# Controller_Board_Interface.net
KiCad netlist of a schematic drawn in Altium Designer
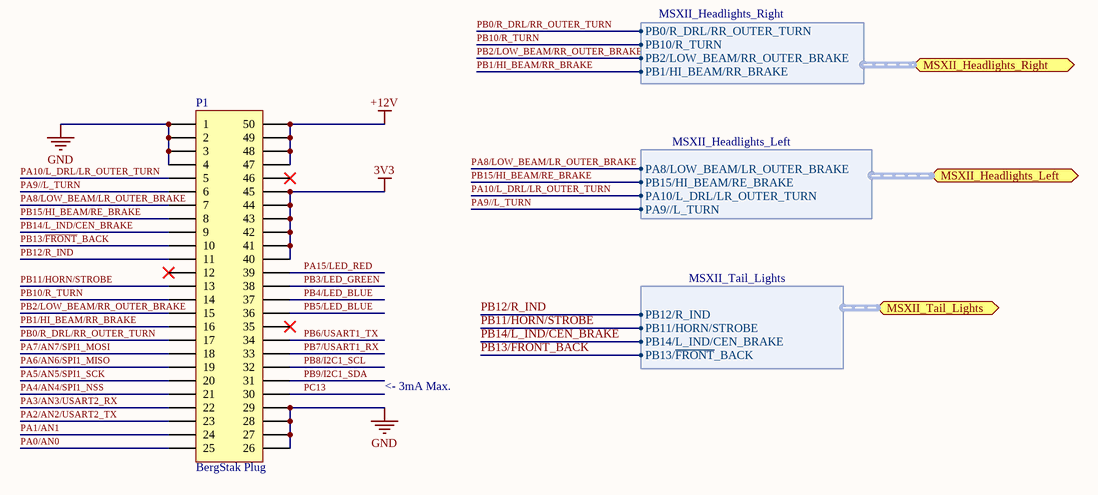
[diagram p0: Controller_Board_Interface.SchDoc]

(export (version "E")
  (design (tool "Eeschema 10.0.6"))
  (components
    (comp (ref "P1")
      (value "CONN 50POS Bergstak Plug 0.02\"")
      (footprint "CONN, Bergstak 50 Pos Plug")
      (description "50 Position Connector Plug, Outer Shroud Contacts Surface Mount Gold")
      (fields (field (name "SERIES") "BergStak Plug"))
      (libsource (lib "Schematic Diagrams") (part "CONN 50POS Bergstak Plug 0.02{dblquote}"))
    )
  )
  (nets
    (net (code "4") (name "+12V") (class "Default")
      (node (ref "P1") (pin "47") (pinfunction "47_47") (pintype "passive"))
      (node (ref "P1") (pin "48") (pinfunction "48_48") (pintype "passive"))
      (node (ref "P1") (pin "49") (pinfunction "49_49") (pintype "passive"))
      (node (ref "P1") (pin "50") (pinfunction "50_50") (pintype "passive"))
    )
    (net (code "5") (name "/PA0{slash}AN0") (class "Default")
      (node (ref "P1") (pin "25") (pinfunction "25_25") (pintype "passive"))
    )
    (net (code "6") (name "/PA1{slash}AN1") (class "Default")
      (node (ref "P1") (pin "24") (pinfunction "24_24") (pintype "passive"))
    )
    (net (code "7") (name "/PA2{slash}AN2{slash}USART2_TX") (class "Default")
      (node (ref "P1") (pin "23") (pinfunction "23_23") (pintype "passive"))
    )
    (net (code "8") (name "/PA3{slash}AN3{slash}USART2_RX") (class "Default")
      (node (ref "P1") (pin "22") (pinfunction "22_22") (pintype "passive"))
    )
    (net (code "9") (name "/PA4{slash}AN4{slash}SPI1_NSS") (class "Default")
      (node (ref "P1") (pin "21") (pinfunction "21_21") (pintype "passive"))
    )
    (net (code "10") (name "/PA5{slash}AN5{slash}SPI1_SCK") (class "Default")
      (node (ref "P1") (pin "20") (pinfunction "20_20") (pintype "passive"))
    )
    (net (code "11") (name "/PA6{slash}AN6{slash}SPI1_MISO") (class "Default")
      (node (ref "P1") (pin "19") (pinfunction "19_19") (pintype "passive"))
    )
    (net (code "12") (name "/PA7{slash}AN7{slash}SPI1_MOSI") (class "Default")
      (node (ref "P1") (pin "18") (pinfunction "18_18") (pintype "passive"))
    )
    (net (code "13") (name "/PA8{slash}LOW_BEAM{slash}LR_OUTER_BRAKE") (class "Default")
      (node (ref "P1") (pin "7") (pinfunction "7_7") (pintype "passive"))
    )
    (net (code "14") (name "/PA9{slash}{slash}L_TURN") (class "Default")
      (node (ref "P1") (pin "6") (pinfunction "6_6") (pintype "passive"))
    )
    (net (code "15") (name "/PA10{slash}L_DRL{slash}LR_OUTER_TURN") (class "Default")
      (node (ref "P1") (pin "5") (pinfunction "5_5") (pintype "passive"))
    )
    (net (code "16") (name "/PA15{slash}LED_RED") (class "Default")
      (node (ref "P1") (pin "39") (pinfunction "39_39") (pintype "passive"))
    )
    (net (code "17") (name "/PB0{slash}R_DRL{slash}RR_OUTER_TURN") (class "Default")
      (node (ref "P1") (pin "17") (pinfunction "17_17") (pintype "passive"))
    )
    (net (code "18") (name "/PB1{slash}HI_BEAM{slash}RR_BRAKE") (class "Default")
      (node (ref "P1") (pin "16") (pinfunction "16_16") (pintype "passive"))
    )
    (net (code "19") (name "/PB2{slash}LOW_BEAM{slash}RR_OUTER_BRAKE") (class "Default")
      (node (ref "P1") (pin "15") (pinfunction "15_15") (pintype "passive"))
    )
    (net (code "20") (name "/PB3{slash}LED_GREEN") (class "Default")
      (node (ref "P1") (pin "38") (pinfunction "38_38") (pintype "passive"))
    )
    (net (code "21") (name "/PB4{slash}LED_BLUE") (class "Default")
      (node (ref "P1") (pin "37") (pinfunction "37_37") (pintype "passive"))
    )
    (net (code "22") (name "/PB5{slash}LED_BLUE") (class "Default")
      (node (ref "P1") (pin "36") (pinfunction "36_36") (pintype "passive"))
    )
    (net (code "23") (name "/PB6{slash}USART1_TX") (class "Default")
      (node (ref "P1") (pin "34") (pinfunction "34_34") (pintype "passive"))
    )
    (net (code "24") (name "/PB7{slash}USART1_RX") (class "Default")
      (node (ref "P1") (pin "33") (pinfunction "33_33") (pintype "passive"))
    )
    (net (code "25") (name "/PB8{slash}I2C1_SCL") (class "Default")
      (node (ref "P1") (pin "32") (pinfunction "32_32") (pintype "passive"))
    )
    (net (code "26") (name "/PB9{slash}I2C1_SDA") (class "Default")
      (node (ref "P1") (pin "31") (pinfunction "31_31") (pintype "passive"))
    )
    (net (code "27") (name "/PB10{slash}R_TURN") (class "Default")
      (node (ref "P1") (pin "14") (pinfunction "14_14") (pintype "passive"))
    )
    (net (code "28") (name "/PB11{slash}HORN{slash}STROBE") (class "Default")
      (node (ref "P1") (pin "13") (pinfunction "13_13") (pintype "passive"))
    )
    (net (code "29") (name "/PB12{slash}R_IND") (class "Default")
      (node (ref "P1") (pin "11") (pinfunction "11_11") (pintype "passive"))
    )
    (net (code "30") (name "/PB13{slash}~{FRONT}_BACK") (class "Default")
      (node (ref "P1") (pin "10") (pinfunction "10_10") (pintype "passive"))
    )
    (net (code "31") (name "/PB14{slash}L_IND{slash}CEN_BRAKE") (class "Default")
      (node (ref "P1") (pin "9") (pinfunction "9_9") (pintype "passive"))
    )
    (net (code "32") (name "/PB15{slash}HI_BEAM{slash}RE_BRAKE") (class "Default")
      (node (ref "P1") (pin "8") (pinfunction "8_8") (pintype "passive"))
    )
    (net (code "33") (name "/PC13") (class "Default")
      (node (ref "P1") (pin "30") (pinfunction "30_30") (pintype "passive"))
    )
    (net (code "37") (name "3V3") (class "Default")
      (node (ref "P1") (pin "40") (pinfunction "40_40") (pintype "passive"))
      (node (ref "P1") (pin "41") (pinfunction "41_41") (pintype "passive"))
      (node (ref "P1") (pin "42") (pinfunction "42_42") (pintype "passive"))
      (node (ref "P1") (pin "43") (pinfunction "43_43") (pintype "passive"))
      (node (ref "P1") (pin "44") (pinfunction "44_44") (pintype "passive"))
      (node (ref "P1") (pin "45") (pinfunction "45_45") (pintype "passive"))
    )
    (net (code "38") (name "GND") (class "Default")
      (node (ref "P1") (pin "1") (pinfunction "1_1") (pintype "passive"))
      (node (ref "P1") (pin "2") (pinfunction "2_2") (pintype "passive"))
      (node (ref "P1") (pin "26") (pinfunction "26_26") (pintype "passive"))
      (node (ref "P1") (pin "27") (pinfunction "27_27") (pintype "passive"))
      (node (ref "P1") (pin "28") (pinfunction "28_28") (pintype "passive"))
      (node (ref "P1") (pin "29") (pinfunction "29_29") (pintype "passive"))
      (node (ref "P1") (pin "3") (pinfunction "3_3") (pintype "passive"))
      (node (ref "P1") (pin "4") (pinfunction "4_4") (pintype "passive"))
    )
    (net (code "39") (name "unconnected-(P1-Pad12)") (class "Default")
      (node (ref "P1") (pin "12") (pinfunction "12_12") (pintype "passive+no_connect"))
    )
    (net (code "40") (name "unconnected-(P1-Pad35)") (class "Default")
      (node (ref "P1") (pin "35") (pinfunction "35_35") (pintype "passive+no_connect"))
    )
    (net (code "41") (name "unconnected-(P1-Pad46)") (class "Default")
      (node (ref "P1") (pin "46") (pinfunction "46_46") (pintype "passive+no_connect"))
    )
  )
)
